# Lab7-8_CH2.net
KiCad netlist of a schematic drawn in Altium Designer
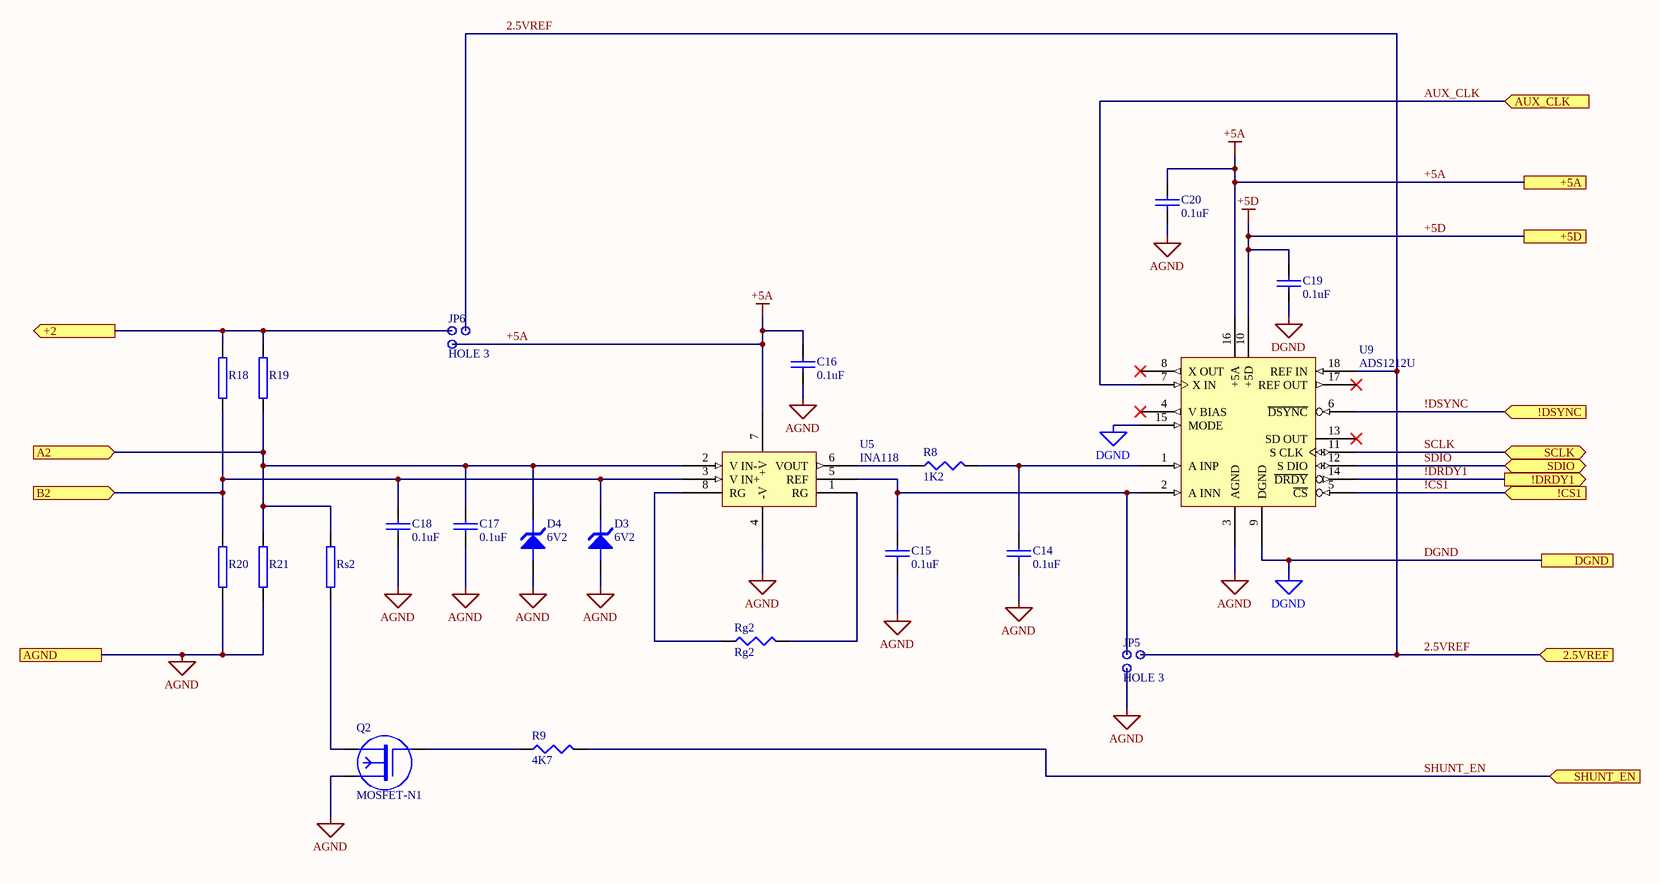
[diagram p0: Lab7-8_CH2.SchDoc]

(export (version "E")
  (design (tool "Eeschema 10.0.6"))
  (components
    (comp (ref "C14")
      (value "0.1uF")
      (footprint "0805")
      (libsource (lib "ECET231_ProjectThree_SCHLIB_Rev02") (part "CAP"))
    )
    (comp (ref "C15")
      (value "0.1uF")
      (footprint "0805")
      (libsource (lib "ECET231_ProjectThree_SCHLIB_Rev02") (part "CAP"))
    )
    (comp (ref "C16")
      (value "0.1uF")
      (footprint "0805")
      (libsource (lib "ECET231_ProjectThree_SCHLIB_Rev02") (part "CAP"))
    )
    (comp (ref "C17")
      (value "0.1uF")
      (footprint "0805")
      (libsource (lib "ECET231_ProjectThree_SCHLIB_Rev02") (part "CAP"))
    )
    (comp (ref "C18")
      (value "0.1uF")
      (footprint "0805")
      (libsource (lib "ECET231_ProjectThree_SCHLIB_Rev02") (part "CAP"))
    )
    (comp (ref "C19")
      (value "0.1uF")
      (footprint "0805")
      (libsource (lib "ECET231_ProjectThree_SCHLIB_Rev02") (part "CAP"))
    )
    (comp (ref "C20")
      (value "0.1uF")
      (footprint "0805")
      (libsource (lib "ECET231_ProjectThree_SCHLIB_Rev02") (part "CAP"))
    )
    (comp (ref "D3")
      (value "6V2")
      (footprint "SOD-123")
      (libsource (lib "ECET231_ProjectThree_SCHLIB_Rev02") (part "ZENER3"))
    )
    (comp (ref "D4")
      (value "6V2")
      (footprint "SOD-123")
      (libsource (lib "ECET231_ProjectThree_SCHLIB_Rev02") (part "ZENER3"))
    )
    (comp (ref "JP5")
      (value "HOLE 3")
      (footprint "RAD0.1A")
      (libsource (lib "ECET231_ProjectThree_SCHLIB_Rev02") (part "HOLE 3"))
    )
    (comp (ref "JP6")
      (value "HOLE 3")
      (footprint "RAD0.1A")
      (libsource (lib "ECET231_ProjectThree_SCHLIB_Rev02") (part "HOLE 3"))
    )
    (comp (ref "Q2")
      (value "MOSFET-N1")
      (footprint "SOT-23")
      (libsource (lib "ECET231_ProjectThree_SCHLIB_Rev02") (part "MOSFET-N1"))
    )
    (comp (ref "R8")
      (value "1K2")
      (footprint "0805")
      (libsource (lib "ECET231_ProjectThree_SCHLIB_Rev02") (part "RES1"))
    )
    (comp (ref "R9")
      (value "4K7")
      (footprint "0805")
      (libsource (lib "ECET231_ProjectThree_SCHLIB_Rev02") (part "RES1"))
    )
    (comp (ref "R18")
      (value "bridge R")
      (footprint "bridge resistor")
      (libsource (lib "ECET231_ProjectThree_SCHLIB_Rev02") (part "RES2"))
    )
    (comp (ref "R19")
      (value "bridge R")
      (footprint "bridge resistor")
      (libsource (lib "ECET231_ProjectThree_SCHLIB_Rev02") (part "RES2"))
    )
    (comp (ref "R20")
      (value "bridge R")
      (footprint "bridge resistor")
      (libsource (lib "ECET231_ProjectThree_SCHLIB_Rev02") (part "RES2"))
    )
    (comp (ref "R21")
      (value "bridge R")
      (footprint "bridge resistor")
      (libsource (lib "ECET231_ProjectThree_SCHLIB_Rev02") (part "RES2"))
    )
    (comp (ref "Rg2")
      (value "Rg2")
      (footprint "0805")
      (libsource (lib "ECET231_ProjectThree_SCHLIB_Rev02") (part "RES1"))
    )
    (comp (ref "Rs2")
      (value "bridge R")
      (footprint "bridge resistor")
      (libsource (lib "ECET231_ProjectThree_SCHLIB_Rev02") (part "RES2"))
    )
    (comp (ref "U5")
      (value "INA118")
      (footprint "SO-8")
      (description "Precision, Low Power Instrumentation Amplifier")
      (libsource (lib "ECET231_ProjectThree_SCHLIB_Rev02") (part "INA118"))
    )
    (comp (ref "U9")
      (value "ADS1212U")
      (footprint "SOIC18")
      (description "22-Bit Analog-to-Digital Converter")
      (libsource (lib "ECET231_ProjectThree_SCHLIB_Rev02") (part "ADS1212U(18)"))
    )
  )
  (nets
    (net (code "1") (name "+5A") (class "Default")
      (node (ref "C16") (pin "1") (pintype "passive"))
      (node (ref "C20") (pin "1") (pintype "passive"))
      (node (ref "JP6") (pin "1") (pinfunction "1_1") (pintype "passive"))
      (node (ref "U5") (pin "7") (pinfunction "+V_7") (pintype "power_in"))
      (node (ref "U9") (pin "16") (pinfunction "+5A_16") (pintype "power_in"))
    )
    (net (code "2") (name "+5D") (class "Default")
      (node (ref "C19") (pin "1") (pintype "passive"))
      (node (ref "U9") (pin "10") (pinfunction "+5D_10") (pintype "power_in"))
    )
    (net (code "3") (name "/!CS1") (class "Default")
      (node (ref "U9") (pin "5") (pinfunction "~{CS}_5") (pintype "input"))
    )
    (net (code "4") (name "/!DRDY1") (class "Default")
      (node (ref "U9") (pin "14") (pinfunction "~{DRDY}_14") (pintype "output"))
    )
    (net (code "5") (name "/!DSYNC") (class "Default")
      (node (ref "U9") (pin "6") (pinfunction "~{DSYNC}_6") (pintype "input"))
    )
    (net (code "6") (name "/+2") (class "Default")
      (node (ref "JP6") (pin "2") (pinfunction "2_2") (pintype "passive"))
      (node (ref "R18") (pin "2") (pintype "passive"))
      (node (ref "R19") (pin "2") (pintype "passive"))
    )
    (net (code "7") (name "/2.5VREF") (class "Default")
      (node (ref "JP5") (pin "3") (pinfunction "3_3") (pintype "passive"))
      (node (ref "JP6") (pin "3") (pinfunction "3_3") (pintype "passive"))
      (node (ref "U9") (pin "18") (pinfunction "REF_IN_18") (pintype "input"))
    )
    (net (code "8") (name "/A2") (class "Default")
      (node (ref "C17") (pin "1") (pintype "passive"))
      (node (ref "D4") (pin "K") (pintype "passive"))
      (node (ref "R19") (pin "1") (pintype "passive"))
      (node (ref "R21") (pin "2") (pintype "passive"))
      (node (ref "Rs2") (pin "2") (pintype "passive"))
      (node (ref "U5") (pin "2") (pinfunction "V_IN-_2") (pintype "input"))
    )
    (net (code "9") (name "/AUX_CLK") (class "Default")
      (node (ref "U9") (pin "7") (pinfunction "X_IN_7") (pintype "input"))
    )
    (net (code "10") (name "/B2") (class "Default")
      (node (ref "C18") (pin "1") (pintype "passive"))
      (node (ref "D3") (pin "K") (pintype "passive"))
      (node (ref "R18") (pin "1") (pintype "passive"))
      (node (ref "R20") (pin "2") (pintype "passive"))
      (node (ref "U5") (pin "3") (pinfunction "V_IN+_3") (pintype "input"))
    )
    (net (code "11") (name "/SCLK") (class "Default")
      (node (ref "U9") (pin "11") (pinfunction "S_CLK_11") (pintype "bidirectional"))
    )
    (net (code "12") (name "/SDIO") (class "Default")
      (node (ref "U9") (pin "12") (pinfunction "S_DIO_12") (pintype "bidirectional"))
    )
    (net (code "13") (name "/SHUNT_EN") (class "Default") (node (ref "R9") (pin "2") (pintype "passive")))
    (net (code "14") (name "AGND") (class "Default")
      (node (ref "C14") (pin "2") (pintype "passive"))
      (node (ref "C15") (pin "2") (pintype "passive"))
      (node (ref "C16") (pin "2") (pintype "passive"))
      (node (ref "C17") (pin "2") (pintype "passive"))
      (node (ref "C18") (pin "2") (pintype "passive"))
      (node (ref "C20") (pin "2") (pintype "passive"))
      (node (ref "D3") (pin "A") (pintype "passive"))
      (node (ref "D4") (pin "A") (pintype "passive"))
      (node (ref "JP5") (pin "1") (pinfunction "1_1") (pintype "passive"))
      (node (ref "Q2") (pin "2") (pintype "passive"))
      (node (ref "R20") (pin "1") (pintype "passive"))
      (node (ref "R21") (pin "1") (pintype "passive"))
      (node (ref "U5") (pin "4") (pinfunction "-V_4") (pintype "power_in"))
      (node (ref "U9") (pin "3") (pinfunction "AGND_3") (pintype "power_in"))
    )
    (net (code "15") (name "DGND") (class "Default")
      (node (ref "C19") (pin "2") (pintype "passive"))
      (node (ref "U9") (pin "15") (pinfunction "MODE_15") (pintype "input"))
      (node (ref "U9") (pin "9") (pinfunction "DGND_9") (pintype "power_in"))
    )
    (net (code "16") (name "Net-(Q2-Pad1)") (class "Default")
      (node (ref "Q2") (pin "1") (pintype "passive"))
      (node (ref "R9") (pin "1") (pintype "passive"))
    )
    (net (code "17") (name "Net-(Q2-Pad3)") (class "Default")
      (node (ref "Q2") (pin "3") (pintype "passive"))
      (node (ref "Rs2") (pin "1") (pintype "passive"))
    )
    (net (code "18") (name "Net-(Rg2-Pad1)") (class "Default")
      (node (ref "Rg2") (pin "1") (pintype "passive"))
      (node (ref "U5") (pin "8") (pinfunction "RG_8") (pintype "passive"))
    )
    (net (code "19") (name "Net-(Rg2-Pad2)") (class "Default")
      (node (ref "Rg2") (pin "2") (pintype "passive"))
      (node (ref "U5") (pin "1") (pinfunction "RG_1") (pintype "passive"))
    )
    (net (code "20") (name "Net-(U5-REF)") (class "Default")
      (node (ref "C15") (pin "1") (pintype "passive"))
      (node (ref "JP5") (pin "2") (pinfunction "2_2") (pintype "passive"))
      (node (ref "U5") (pin "5") (pinfunction "REF_5") (pintype "passive"))
      (node (ref "U9") (pin "2") (pinfunction "A_INN_2") (pintype "input"))
    )
    (net (code "21") (name "Net-(U5-VOUT)") (class "Default")
      (node (ref "R8") (pin "1") (pintype "passive"))
      (node (ref "U5") (pin "6") (pinfunction "VOUT_6") (pintype "output"))
    )
    (net (code "22") (name "Net-(U9-A_INP)") (class "Default")
      (node (ref "C14") (pin "1") (pintype "passive"))
      (node (ref "R8") (pin "2") (pintype "passive"))
      (node (ref "U9") (pin "1") (pinfunction "A_INP_1") (pintype "input"))
    )
    (net (code "23") (name "unconnected-(U9-REF_OUT-Pad17)") (class "Default")
      (node (ref "U9") (pin "17") (pinfunction "REF_OUT_17") (pintype "output+no_connect"))
    )
    (net (code "24") (name "unconnected-(U9-SD_OUT-Pad13)") (class "Default")
      (node (ref "U9") (pin "13") (pinfunction "SD_OUT_13") (pintype "tri_state+no_connect"))
    )
    (net (code "25") (name "unconnected-(U9-V_BIAS-Pad4)") (class "Default")
      (node (ref "U9") (pin "4") (pinfunction "V_BIAS_4") (pintype "output+no_connect"))
    )
    (net (code "26") (name "unconnected-(U9-X_OUT-Pad8)") (class "Default")
      (node (ref "U9") (pin "8") (pinfunction "X_OUT_8") (pintype "output+no_connect"))
    )
  )
)
